# Bias_High.net
KiCad netlist of a schematic drawn in Altium Designer
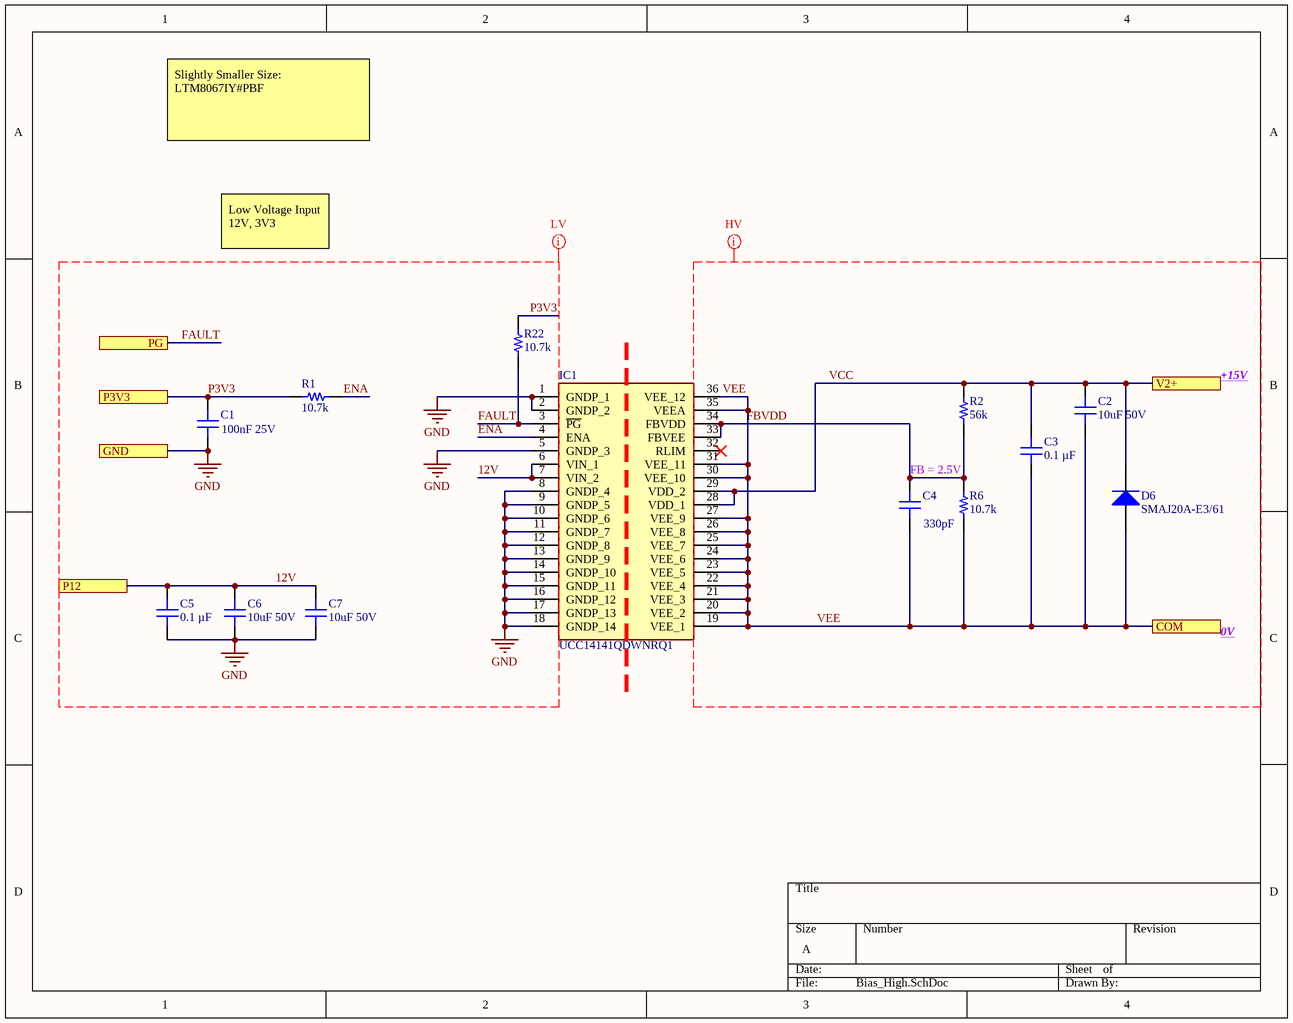
[diagram p0: Bias_High.SchDoc]

(export (version "E")
  (design (tool "Eeschema 10.0.6"))
  (components
    (comp (ref "C1")
      (value "100nF 25V")
      (footprint "CAP 0402_1005")
      (description "CAP CER 10UF 6.3V X5R 0402")
      (fields
        (field (name "PART NUMBER") "ZRB15XR60J106ME12D")
        (field (name "MANUFACTURER") "Murata Electronics")
      )
      (libsource (lib "Celestial Altium Library - altium_library") (part "Capacitor"))
    )
    (comp (ref "C2")
      (value "10uF 50V")
      (footprint "CAP 1210_3225 - 1MM")
      (description "CAP CER 10UF 25V X5R 1210")
      (fields (field (name "PART NUMBER") "MSAST32NSB5106MTNA01") (field (name "MANUFACTURER") "Taiyo Yuden"))
      (libsource (lib "Celestial Altium Library - altium_library") (part "Capacitor"))
    )
    (comp (ref "C3")
      (value "0.1 µF")
      (footprint "CAP 0603_1608")
      (description "CAP CER 0.1UF 50V X7R 0603")
      (fields
        (field (name "PART NUMBER") "C0603C104K5RAC7411")
        (field (name "CAPACITANCE") "0.1 µF")
        (field (name "MANUFACTURER") "KEMET")
      )
      (libsource (lib "Celestial Altium Library - altium_library") (part "Capacitor"))
    )
    (comp (ref "C4")
      (value "330pF")
      (footprint "CAP 0402_1005")
      (description "CAP CER 10UF 6.3V X5R 0402")
      (fields
        (field (name "PART NUMBER") "ZRB15XR60J106ME12D")
        (field (name "MANUFACTURER") "Murata Electronics")
      )
      (libsource (lib "Celestial Altium Library - altium_library") (part "Capacitor"))
    )
    (comp (ref "C5")
      (value "0.1 µF")
      (footprint "CAP 0603_1608")
      (description "CAP CER 0.1UF 50V X7R 0603")
      (fields
        (field (name "PART NUMBER") "C0603C104K5RAC7411")
        (field (name "CAPACITANCE") "0.1 µF")
        (field (name "MANUFACTURER") "KEMET")
      )
      (libsource (lib "Celestial Altium Library - altium_library") (part "Capacitor"))
    )
    (comp (ref "C6")
      (value "10uF 50V")
      (footprint "CAP 1210_3225 - 1MM")
      (description "CAP CER 10UF 25V X5R 1210")
      (fields (field (name "PART NUMBER") "MSAST32NSB5106MTNA01") (field (name "MANUFACTURER") "Taiyo Yuden"))
      (libsource (lib "Celestial Altium Library - altium_library") (part "Capacitor"))
    )
    (comp (ref "C7")
      (value "10uF 50V")
      (footprint "CAP 1210_3225 - 1MM")
      (description "CAP CER 10UF 25V X5R 1210")
      (fields (field (name "PART NUMBER") "MSAST32NSB5106MTNA01") (field (name "MANUFACTURER") "Taiyo Yuden"))
      (libsource (lib "Celestial Altium Library - altium_library") (part "Capacitor"))
    )
    (comp (ref "D6")
      (value "SMAJ20A-E3/61")
      (footprint "VISH-DO-214AC-2_M")
      (fields (field (name "MANUFACTURER") "Vishay Semiconductor"))
      (libsource (lib "Altium Content Vault") (part "VISH-K1A2-2"))
    )
    (comp (ref "IC1")
      (value "UCC14141QDWNRQ1")
      (footprint "SamacSys:SOP65P1030X355-36N")
      (description "Integrated Circuit")
      (fields (field (name "MOUSER PART NUMBER") "595-UCC14141QDWNRQ1"))
      (libsource (lib "Schlib2") (part "UCC14141QDWNRQ1"))
    )
    (comp (ref "R1")
      (value "10.7k")
      (footprint "RES 0402_1005")
      (description "RES 249K OHM 0.1% 1/10W 0402")
      (fields
        (field (name "PART NUMBER") "RP73PF1E249KBTD")
        (field (name "MANUFACTURER") "TE Connectivity Passive Product")
      )
      (libsource (lib "Celestial Altium Library - altium_library") (part "Resistor"))
    )
    (comp (ref "R2")
      (value "56k")
      (footprint "RES 0402_1005")
      (description "RES 249K OHM 0.1% 1/10W 0402")
      (fields
        (field (name "PART NUMBER") "RP73PF1E249KBTD")
        (field (name "MANUFACTURER") "TE Connectivity Passive Product")
      )
      (libsource (lib "Celestial Altium Library - altium_library") (part "Resistor"))
    )
    (comp (ref "R6")
      (value "10.7k")
      (footprint "RES 0402_1005")
      (description "RES 249K OHM 0.1% 1/10W 0402")
      (fields
        (field (name "PART NUMBER") "RP73PF1E249KBTD")
        (field (name "MANUFACTURER") "TE Connectivity Passive Product")
      )
      (libsource (lib "Celestial Altium Library - altium_library") (part "Resistor"))
    )
    (comp (ref "R22")
      (value "10.7k")
      (footprint "RES 0402_1005")
      (description "RES 249K OHM 0.1% 1/10W 0402")
      (fields
        (field (name "PART NUMBER") "RP73PF1E249KBTD")
        (field (name "MANUFACTURER") "TE Connectivity Passive Product")
      )
      (libsource (lib "Celestial Altium Library - altium_library") (part "Resistor"))
    )
  )
  (nets
    (net (code "1") (name "/12V") (class "Default")
      (node (ref "C5") (pin "2") (pinfunction "2_2") (pintype "passive"))
      (node (ref "C6") (pin "1") (pinfunction "1_1") (pintype "passive"))
      (node (ref "C7") (pin "1") (pinfunction "1_1") (pintype "passive"))
      (node (ref "IC1") (pin "6") (pinfunction "VIN_1_6") (pintype "passive"))
      (node (ref "IC1") (pin "7") (pinfunction "VIN_2_7") (pintype "passive"))
    )
    (net (code "2") (name "/ENA") (class "Default")
      (node (ref "IC1") (pin "4") (pinfunction "ENA_4") (pintype "passive"))
      (node (ref "R1") (pin "1") (pinfunction "1_1") (pintype "passive"))
    )
    (net (code "3") (name "/FAULT") (class "Default")
      (node (ref "IC1") (pin "3") (pinfunction "~{PG}_3") (pintype "passive"))
      (node (ref "R22") (pin "2") (pinfunction "2_2") (pintype "passive"))
    )
    (net (code "4") (name "/FBVDD") (class "Default")
      (node (ref "C4") (pin "2") (pinfunction "2_2") (pintype "passive"))
      (node (ref "IC1") (pin "33") (pinfunction "FBVEE_33") (pintype "passive"))
      (node (ref "IC1") (pin "34") (pinfunction "FBVDD_34") (pintype "passive"))
      (node (ref "R2") (pin "1") (pinfunction "1_1") (pintype "passive"))
      (node (ref "R6") (pin "2") (pinfunction "2_2") (pintype "passive"))
    )
    (net (code "5") (name "/P3V3") (class "Default")
      (node (ref "C1") (pin "2") (pinfunction "2_2") (pintype "passive"))
      (node (ref "R1") (pin "2") (pinfunction "2_2") (pintype "passive"))
      (node (ref "R22") (pin "1") (pinfunction "1_1") (pintype "passive"))
    )
    (net (code "6") (name "/VCC") (class "Default")
      (node (ref "C2") (pin "1") (pinfunction "1_1") (pintype "passive"))
      (node (ref "C3") (pin "2") (pinfunction "2_2") (pintype "passive"))
      (node (ref "D6") (pin "1") (pinfunction "K_1") (pintype "passive"))
      (node (ref "IC1") (pin "28") (pinfunction "VDD_1_28") (pintype "passive"))
      (node (ref "IC1") (pin "29") (pinfunction "VDD_2_29") (pintype "passive"))
      (node (ref "R2") (pin "2") (pinfunction "2_2") (pintype "passive"))
    )
    (net (code "7") (name "/VEE") (class "Default")
      (node (ref "C2") (pin "2") (pinfunction "2_2") (pintype "passive"))
      (node (ref "C3") (pin "1") (pinfunction "1_1") (pintype "passive"))
      (node (ref "C4") (pin "1") (pinfunction "1_1") (pintype "passive"))
      (node (ref "D6") (pin "2") (pinfunction "A_2") (pintype "passive"))
      (node (ref "IC1") (pin "19") (pinfunction "VEE_1_19") (pintype "passive"))
      (node (ref "IC1") (pin "20") (pinfunction "VEE_2_20") (pintype "passive"))
      (node (ref "IC1") (pin "21") (pinfunction "VEE_3_21") (pintype "passive"))
      (node (ref "IC1") (pin "22") (pinfunction "VEE_4_22") (pintype "passive"))
      (node (ref "IC1") (pin "23") (pinfunction "VEE_5_23") (pintype "passive"))
      (node (ref "IC1") (pin "24") (pinfunction "VEE_6_24") (pintype "passive"))
      (node (ref "IC1") (pin "25") (pinfunction "VEE_7_25") (pintype "passive"))
      (node (ref "IC1") (pin "26") (pinfunction "VEE_8_26") (pintype "passive"))
      (node (ref "IC1") (pin "27") (pinfunction "VEE_9_27") (pintype "passive"))
      (node (ref "IC1") (pin "30") (pinfunction "VEE_10_30") (pintype "passive"))
      (node (ref "IC1") (pin "31") (pinfunction "VEE_11_31") (pintype "passive"))
      (node (ref "IC1") (pin "35") (pinfunction "VEEA_35") (pintype "passive"))
      (node (ref "IC1") (pin "36") (pinfunction "VEE_12_36") (pintype "passive"))
      (node (ref "R6") (pin "1") (pinfunction "1_1") (pintype "passive"))
    )
    (net (code "8") (name "GND") (class "Default")
      (node (ref "C1") (pin "1") (pinfunction "1_1") (pintype "passive"))
      (node (ref "C5") (pin "1") (pinfunction "1_1") (pintype "passive"))
      (node (ref "C6") (pin "2") (pinfunction "2_2") (pintype "passive"))
      (node (ref "C7") (pin "2") (pinfunction "2_2") (pintype "passive"))
      (node (ref "IC1") (pin "1") (pinfunction "GNDP_1_1") (pintype "passive"))
      (node (ref "IC1") (pin "10") (pinfunction "GNDP_6_10") (pintype "passive"))
      (node (ref "IC1") (pin "11") (pinfunction "GNDP_7_11") (pintype "passive"))
      (node (ref "IC1") (pin "12") (pinfunction "GNDP_8_12") (pintype "passive"))
      (node (ref "IC1") (pin "13") (pinfunction "GNDP_9_13") (pintype "passive"))
      (node (ref "IC1") (pin "14") (pinfunction "GNDP_10_14") (pintype "passive"))
      (node (ref "IC1") (pin "15") (pinfunction "GNDP_11_15") (pintype "passive"))
      (node (ref "IC1") (pin "16") (pinfunction "GNDP_12_16") (pintype "passive"))
      (node (ref "IC1") (pin "17") (pinfunction "GNDP_13_17") (pintype "passive"))
      (node (ref "IC1") (pin "18") (pinfunction "GNDP_14_18") (pintype "passive"))
      (node (ref "IC1") (pin "2") (pinfunction "GNDP_2_2") (pintype "passive"))
      (node (ref "IC1") (pin "5") (pinfunction "GNDP_3_5") (pintype "passive"))
      (node (ref "IC1") (pin "8") (pinfunction "GNDP_4_8") (pintype "passive"))
      (node (ref "IC1") (pin "9") (pinfunction "GNDP_5_9") (pintype "passive"))
    )
    (net (code "9") (name "unconnected-(IC1-RLIM-Pad32)") (class "Default")
      (node (ref "IC1") (pin "32") (pinfunction "RLIM_32") (pintype "passive+no_connect"))
    )
  )
)
